# ModuloQuimica.net
KiCad netlist of a schematic drawn in Altium Designer
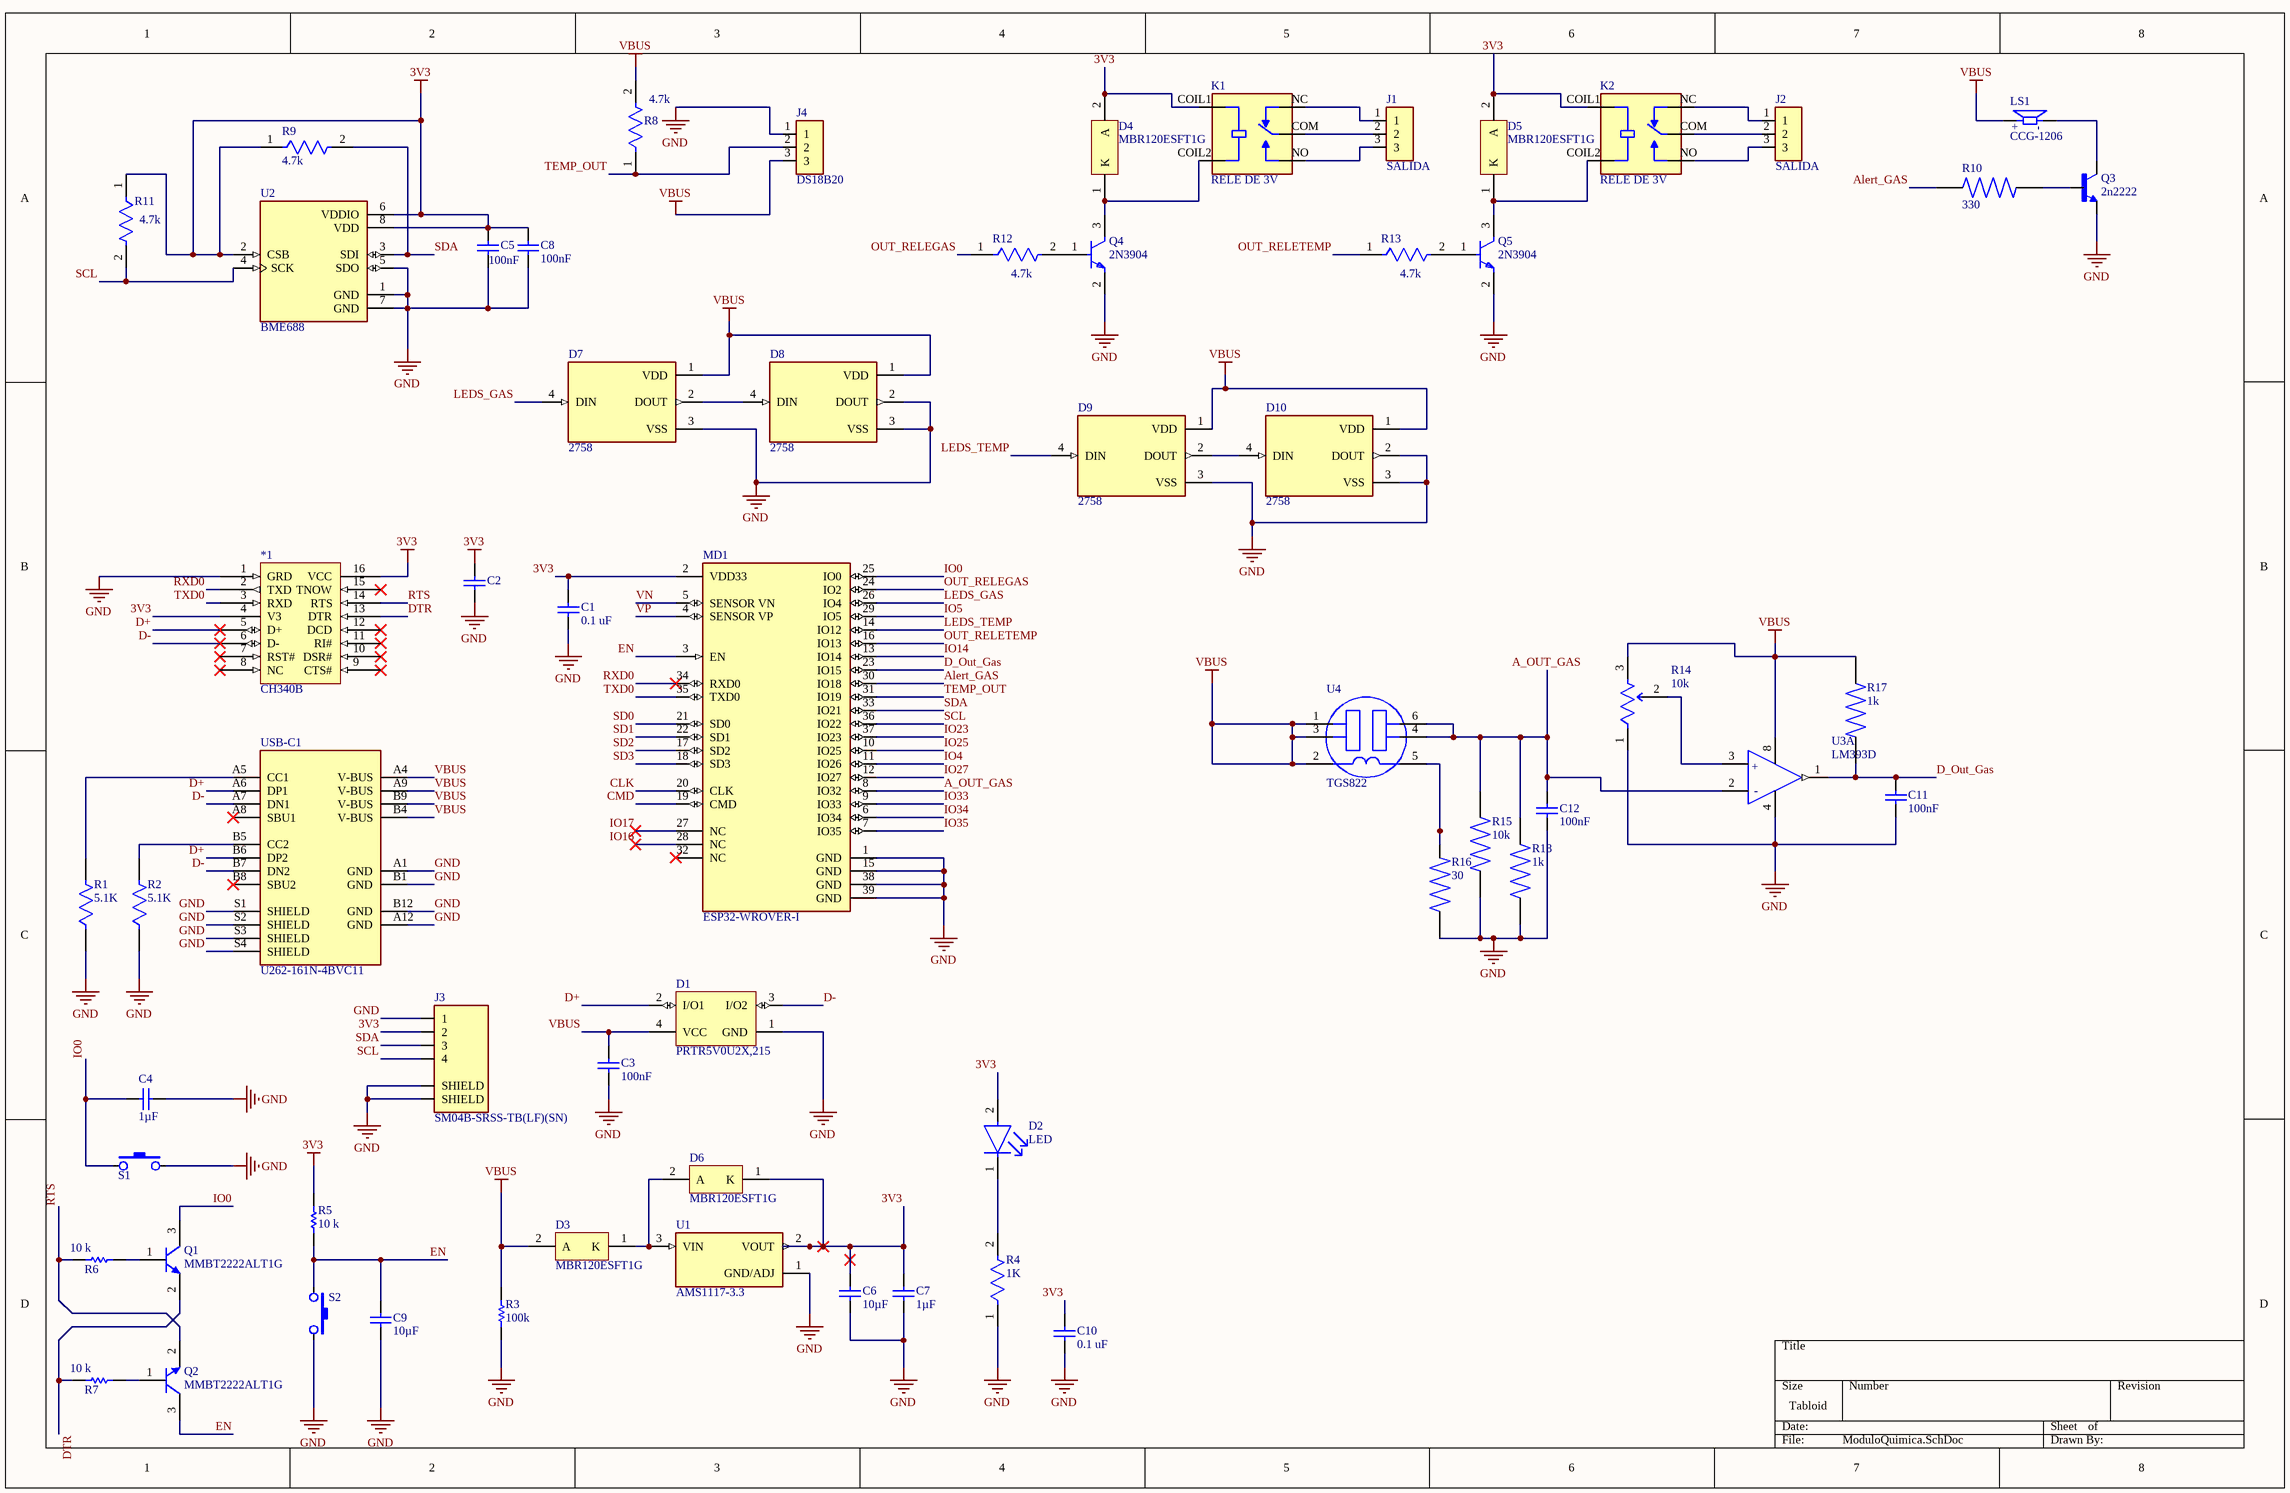
[diagram p0: ModuloQuimica.SchDoc]

(export (version "E")
  (design (tool "Eeschema 10.0.6"))
  (components
    (comp (ref "*1")
      (value "CH340B")
      (footprint "CH340B")
      (description "- USB 2.0 Transceiver 2Mbps SOP-16_150mil USB ICs ROHS")
      (libsource (lib "Isidro_Library") (part "CH340B"))
    )
    (comp (ref "C1")
      (value "0.1 uF")
      (footprint "CAPC2013X94X50ML20T25")
      (description "Chip Capacitor, Ceramic, 0.1 uF, 10%, 50 V, 0805, RoHS, Tape and Reel")
      (fields (field (name "MANUFACTURER") "AVX"))
      (libsource (lib "Altium Content Vault") (part "CAP-NP-2"))
    )
    (comp (ref "C2")
      (value "08055C104KAT2A")
      (footprint "CAPC2013X94X50ML20T25")
      (description "Chip Capacitor, Ceramic, 0.1 uF, 10%, 50 V, 0805, RoHS, Tape and Reel")
      (fields (field (name "MANUFACTURER") "AVX"))
      (libsource (lib "Altium Content Vault") (part "CAP-NP-2"))
    )
    (comp (ref "C3")
      (value "100nF")
      (footprint "CAPC2013X94X50ML20T25")
      (description "Chip Capacitor, Ceramic, 0.1 uF, 10%, 50 V, 0805, RoHS, Tape and Reel")
      (fields (field (name "MANUFACTURER") "AVX"))
      (libsource (lib "Altium Content Vault") (part "CAP-NP-2"))
    )
    (comp (ref "C4")
      (value "1µF")
      (footprint "CAPC2013X145X50ML20T25")
      (description "1µF ±10% 16V Ceramic Capacitor X7R 0805 (2012 Metric)")
      (fields (field (name "MANUFACTURER") "Kemet") (field (name "PART NUMBER") "C0805C105K4RAC7800"))
      (libsource (lib "Altium Content Vault") (part "CAP"))
    )
    (comp (ref "C5")
      (value "100nF")
      (footprint "CAPC2013X145X20LL20")
      (description "Chip Capacitor, 0.1 uF, +/- 10%, 50 V, -55 to 125 degC, 0805 (2012 Metric), RoHS, Tape and Reel")
      (fields (field (name "MANUFACTURER") "TDK") (field (name "VOLTAGE") "50V"))
      (libsource (lib "Altium Content Vault") (part "CAP-NP-2"))
    )
    (comp (ref "C6")
      (value "10µF")
      (footprint "CAPC2013X140X50ML20T25")
      (description "10µF ±10% 16V Ceramic Capacitor X5R 0805 (2012 Metric)")
      (fields (field (name "PART NUMBER") "CL21A106KOQNNNG"))
      (libsource (lib "Altium Content Vault") (part "CAP"))
    )
    (comp (ref "C7")
      (value "1µF")
      (footprint "CAPC2013X145X50ML20T25")
      (description "1µF ±10% 16V Ceramic Capacitor X7R 0805 (2012 Metric)")
      (fields (field (name "MANUFACTURER") "Kemet") (field (name "PART NUMBER") "C0805C105K4RAC7800"))
      (libsource (lib "Altium Content Vault") (part "CAP"))
    )
    (comp (ref "C8")
      (value "100nF")
      (footprint "CAPC2013X145X20LL20")
      (description "Chip Capacitor, 0.1 uF, +/- 10%, 50 V, -55 to 125 degC, 0805 (2012 Metric), RoHS, Tape and Reel")
      (fields (field (name "MANUFACTURER") "TDK") (field (name "VOLTAGE") "50V"))
      (libsource (lib "Altium Content Vault") (part "CAP-NP-2"))
    )
    (comp (ref "C9")
      (value "10µF")
      (footprint "CAPC2013X145X50ML20T25")
      (description "1µF ±10% 16V Ceramic Capacitor X7R 0805 (2012 Metric)")
      (fields (field (name "MANUFACTURER") "Kemet") (field (name "PART NUMBER") "C0805C105K4RAC7800"))
      (libsource (lib "Altium Content Vault") (part "CAP"))
    )
    (comp (ref "C10")
      (value "0.1 uF")
      (footprint "CAPC2013X94X50ML20T25")
      (description "Chip Capacitor, Ceramic, 0.1 uF, 10%, 50 V, 0805, RoHS, Tape and Reel")
      (fields (field (name "MANUFACTURER") "AVX"))
      (libsource (lib "Altium Content Vault") (part "CAP-NP-2"))
    )
    (comp (ref "C11")
      (value "100nF")
      (footprint "CAPC2013X145X20LL20")
      (description "Chip Capacitor, 0.1 uF, +/- 10%, 50 V, -55 to 125 degC, 0805 (2012 Metric), RoHS, Tape and Reel")
      (fields (field (name "MANUFACTURER") "TDK") (field (name "VOLTAGE") "50V"))
      (libsource (lib "Altium Content Vault") (part "CAP-NP-2"))
    )
    (comp (ref "C12")
      (value "100nF")
      (footprint "CAPC2013X145X20LL20")
      (description "Chip Capacitor, 0.1 uF, +/- 10%, 50 V, -55 to 125 degC, 0805 (2012 Metric), RoHS, Tape and Reel")
      (fields (field (name "MANUFACTURER") "TDK") (field (name "VOLTAGE") "50V"))
      (libsource (lib "Altium Content Vault") (part "CAP-NP-2"))
    )
    (comp (ref "D1")
      (value "PRTR5V0U2X,215")
      (footprint "NXP-SOT143B-4_V")
      (fields (field (name "MANUFACTURER") "NXP Semiconductors"))
      (libsource (lib "Altium Content Vault") (part "NXP-PRTR5V0U2X,215-4"))
    )
    (comp (ref "D2")
      (value "LED")
      (footprint "FP-HSMG-C150-MFG")
      (description "LED GREEN DIFFUSED 1206 SMD")
      (fields (field (name "MANUFACTURER PART NUMBER") "HSMG-C150") (field (name "MANUFACTURER") "Broadcom"))
      (libsource (lib "Altium Content Vault") (part "8706943c75ba83719d021d2fdc84c58"))
    )
    (comp (ref "D3")
      (value "MBR120ESFT1G")
      (footprint "ONSC-SOD-123FL-2-498_V")
      (description "Schottky Power Rectifier, 2-Pin SOD-123, Pb-Free, Tape and Reel")
      (fields (field (name "MANUFACTURER") "On Semiconductor"))
      (libsource (lib "Altium Content Vault") (part "ONSC-D-K1A2-2_A"))
    )
    (comp (ref "D4")
      (value "MBR120ESFT1G")
      (footprint "ONSC-SOD-123FL-2-498_V")
      (description "Schottky Power Rectifier, 2-Pin SOD-123, Pb-Free, Tape and Reel")
      (fields (field (name "MANUFACTURER") "On Semiconductor"))
      (libsource (lib "") (part "ONSC-D-K1A2-2_A_1"))
    )
    (comp (ref "D5")
      (value "MBR120ESFT1G")
      (footprint "ONSC-SOD-123FL-2-498_V")
      (description "Schottky Power Rectifier, 2-Pin SOD-123, Pb-Free, Tape and Reel")
      (fields (field (name "MANUFACTURER") "On Semiconductor"))
      (libsource (lib "") (part "ONSC-D-K1A2-2_A_1"))
    )
    (comp (ref "D6")
      (value "MBR120ESFT1G")
      (footprint "ONSC-SOD-123FL-2-498_V")
      (description "Schottky Power Rectifier, 2-Pin SOD-123, Pb-Free, Tape and Reel")
      (fields (field (name "MANUFACTURER") "On Semiconductor"))
      (libsource (lib "Altium Content Vault") (part "ONSC-D-K1A2-2_A"))
    )
    (comp (ref "D7")
      (value "2758")
      (footprint "SOL320P540X170-4N")
      (description "NeoPixel RGBW LEDs w/ Integrated DriverChip - Natural White - 4500K - White Ca")
      (fields (field (name "MF") "Adafruit Industries"))
      (libsource (lib "2758") (part "2758"))
    )
    (comp (ref "D8")
      (value "2758")
      (footprint "SOL320P540X170-4N")
      (description "NeoPixel RGBW LEDs w/ Integrated DriverChip - Natural White - 4500K - White Ca")
      (fields (field (name "MF") "Adafruit Industries"))
      (libsource (lib "2758") (part "2758"))
    )
    (comp (ref "D9")
      (value "2758")
      (footprint "SOL320P540X170-4N")
      (description "NeoPixel RGBW LEDs w/ Integrated DriverChip - Natural White - 4500K - White Ca")
      (fields (field (name "MF") "Adafruit Industries"))
      (libsource (lib "2758") (part "2758"))
    )
    (comp (ref "D10")
      (value "2758")
      (footprint "SOL320P540X170-4N")
      (description "NeoPixel RGBW LEDs w/ Integrated DriverChip - Natural White - 4500K - White Ca")
      (fields (field (name "MF") "Adafruit Industries"))
      (libsource (lib "2758") (part "2758"))
    )
    (comp (ref "J1")
      (value "SALIDA")
      (footprint "TE_282836-3")
      (description "TERM BLOCK 3POS SIDE ENTRY 5MM")
      (fields (field (name "MP") "282836-3"))
      (libsource (lib "282836-3") (part "282836-3"))
    )
    (comp (ref "J2")
      (value "SALIDA")
      (footprint "TE_282836-3")
      (description "TERM BLOCK 3POS SIDE ENTRY 5MM")
      (fields (field (name "MP") "282836-3"))
      (libsource (lib "282836-3") (part "282836-3"))
    )
    (comp (ref "J3")
      (value "SM04B-SRSS-TB(LF)(SN)")
      (footprint "JST_SM04B-SRSS-TB(LF)(SN)")
      (description "Connector Header Surface Mount, Right Angle 4 position 0.039 _1.00mm_")
      (fields (field (name "MF") "JST Sales") (field (name "MP") "SM04B-SRSS-TB_LF__SN_"))
      (libsource (lib "Isidro_Library") (part "SM04B-SRSS-TB(LF)(SN)"))
    )
    (comp (ref "J4")
      (value "DS18B20")
      (footprint "TE_282836-3")
      (description "TERM BLOCK 3POS SIDE ENTRY 5MM")
      (fields (field (name "MP") "282836-3"))
      (libsource (lib "282836-3") (part "282836-3"))
    )
    (comp (ref "K1")
      (value "RELE DE 3V")
      (footprint "RELAY_SRD-03VDC-SL-C")
      (description "Relays General Purpose Non Latching 3VDC SPDT 10A (250VAC) Max 5PIN")
      (fields (field (name "MF") "Songle Relay") (field (name "MP") "SRD-03VDC-SL-C"))
      (libsource (lib "SRD-03VDC-SL-C (1)") (part "SRD-03VDC-SL-C"))
    )
    (comp (ref "K2")
      (value "RELE DE 3V")
      (footprint "RELAY_SRD-03VDC-SL-C")
      (description "Relays General Purpose Non Latching 3VDC SPDT 10A (250VAC) Max 5PIN")
      (fields (field (name "MF") "Songle Relay") (field (name "MP") "SRD-03VDC-SL-C"))
      (libsource (lib "SRD-03VDC-SL-C (1)") (part "SRD-03VDC-SL-C"))
    )
    (comp (ref "LS1")
      (value "CCG-1206")
      (footprint "CUI_CCG-1206")
      (description "12 mm, 5 V, 85 dB, Through Hole, Sealed, Magnetic Audio Transducer Buzzer")
      (fields (field (name "MF") "Same Sky"))
      (libsource (lib "CCG-1206") (part "CCG-1206"))
    )
    (comp (ref "MD1")
      (value "ESP32-WROVER-I")
      (footprint "FP-ESP32-WROVER-I-MFG")
      (description "SMD MODULE, ESP32-D0WDQ6, 32MBIT")
      (fields
        (field (name "MANUFACTURER") "Espressif")
        (field (name "OCTOPART") "https://octopart.com/esp32-wrover-i-espressif+systems-89171349")
      )
      (libsource (lib "Altium Content Vault") (part "cbbb37af8bcfe61dfd46ac9418f0340"))
    )
    (comp (ref "Q1")
      (value "MMBT2222ALT1G")
      (footprint "ONSC-SOT-23-3-318-08_V")
      (description "General Purpose Transistor, NPN Silicon, 3-Pin SOT-23, Pb-Free, Tape and Reel")
      (fields (field (name "MANUFACTURER") "On Semiconductor"))
      (libsource (lib "Altium Content Vault") (part "ONSC-NPN-B1E2C3-3"))
    )
    (comp (ref "Q2")
      (value "MMBT2222ALT1G")
      (footprint "ONSC-SOT-23-3-318-08_V")
      (description "General Purpose Transistor, NPN Silicon, 3-Pin SOT-23, Pb-Free, Tape and Reel")
      (fields (field (name "MANUFACTURER") "On Semiconductor"))
      (libsource (lib "Altium Content Vault") (part "ONSC-NPN-B1E2C3-3"))
    )
    (comp (ref "Q3")
      (value "2n2222")
      (footprint "SOT95P240X120-3N")
      (description "BJT, SOT-23, 40V, 600mA, NPN, 0.25W, 150Â°C")
      (fields (field (name "MF") "Diotec Semiconductor") (field (name "MP") "MMBT2222A"))
      (libsource (lib "MMBT2222A") (part "MMBT2222A"))
    )
    (comp (ref "Q4")
      (value "2N3904")
      (footprint "FP-SS8050-G-MFG")
      (description "NPN TRANSISTOR 1.5A 40V SOT-23 R")
      (libsource (lib "Altium Content Vault") (part "2a1388f82443b098dcd57d24ac7632d"))
    )
    (comp (ref "Q5")
      (value "2N3904")
      (footprint "FP-SS8050-G-MFG")
      (description "NPN TRANSISTOR 1.5A 40V SOT-23 R")
      (libsource (lib "Altium Content Vault") (part "2a1388f82443b098dcd57d24ac7632d"))
    )
    (comp (ref "R1")
      (value "5.1K")
      (footprint "FP-CRCW0805-e3-MFG")
      (description "RES Thick Film, 5.1kΩ, 1%, 0.125W, 100ppm/°C, 0805")
      (fields (field (name "TOLERANCE") "1%"))
      (libsource (lib "Altium Content Vault") (part "1029c3af85768c4190bb7ad29bc67b5"))
    )
    (comp (ref "R2")
      (value "5.1K")
      (footprint "FP-CRCW0805-e3-MFG")
      (description "RES Thick Film, 5.1kΩ, 1%, 0.125W, 100ppm/°C, 0805")
      (fields (field (name "TOLERANCE") "1%"))
      (libsource (lib "Altium Content Vault") (part "1029c3af85768c4190bb7ad29bc67b5"))
    )
    (comp (ref "R3")
      (value "100k")
      (footprint "RESC2013X60X40ML20T25")
      (description "100 kOhms ±0.1% 0.125W, 1/8W Chip Resistor 0805 (2012 Metric) Automotive AEC-Q200 Thin Film")
      (fields (field (name "PART NUMBER") "ERA6AEB104V") (field (name "MANUFACTURER") "Panasonic"))
      (libsource (lib "Altium Content Vault") (part "RES"))
    )
    (comp (ref "R4")
      (value "1K")
      (footprint "FP-RP732A-MFG")
      (description "RESISTOR, 0805 80.6Ω, 0.1% 15ppm/°C")
      (fields
        (field (name "OCTOPART") "https://octopart.com/rp73d2a80r6btg-te+connectivity-42011633")
        (field (name "MANUFACTURER") "TE Connectivity")
      )
      (libsource (lib "") (part "1029c3af85768c4190bb7ad29bc67b5_1"))
    )
    (comp (ref "R5")
      (value "10 k")
      (footprint "RESC2013X60X30ML20T20")
      (fields (field (name "PART NUMBER") "RK73B2ATTD103J") (field (name "MANUFACTURER") "KOA Speer"))
      (libsource (lib "Altium Content Vault") (part "RES"))
    )
    (comp (ref "R6")
      (value "10 k")
      (footprint "RESC2013X60X30ML20T20")
      (fields (field (name "PART NUMBER") "RK73B2ATTD103J") (field (name "MANUFACTURER") "KOA Speer"))
      (libsource (lib "Altium Content Vault") (part "RES"))
    )
    (comp (ref "R7")
      (value "10 k")
      (footprint "RESC2013X60X30ML20T20")
      (fields (field (name "PART NUMBER") "RK73B2ATTD103J") (field (name "MANUFACTURER") "KOA Speer"))
      (libsource (lib "Altium Content Vault") (part "RES"))
    )
    (comp (ref "R8")
      (value "4.7k")
      (footprint "FP-CR1206-MFG")
      (description "Thick Film Chip Resistors 1206 4.7kΩ 0.25W 1% 100ppm/°C")
      (fields (field (name "TOLERANCE") "1%"))
      (libsource (lib "") (part "1029c3af85768c4190bb7ad29bc67b5_1"))
    )
    (comp (ref "R9")
      (value "4.7k")
      (footprint "FP-CR1206-MFG")
      (description "Thick Film Chip Resistors 1206 4.7kΩ 0.25W 1% 100ppm/°C")
      (fields (field (name "TOLERANCE") "1%"))
      (libsource (lib "") (part "1029c3af85768c4190bb7ad29bc67b5_1"))
    )
    (comp (ref "R10")
      (value "330")
      (footprint "RESC3015X65N")
      (description "330 Ohms Â±5% 0.25W, 1/4W Chip Resistor 1206 (3216 Metric) Thick Film")
      (fields (field (name "MF") "Vishay") (field (name "MP") "CRCW1206330RJNEAC"))
      (libsource (lib "CRCW1206330RJNEAC") (part "CRCW1206330RJNEAC"))
    )
    (comp (ref "R11")
      (value "4.7k")
      (footprint "FP-CR1206-MFG")
      (description "Thick Film Chip Resistors 1206 4.7kΩ 0.25W 1% 100ppm/°C")
      (fields (field (name "TOLERANCE") "1%"))
      (libsource (lib "") (part "1029c3af85768c4190bb7ad29bc67b5_1"))
    )
    (comp (ref "R12")
      (value "4.7k")
      (footprint "FP-CR1206-MFG")
      (description "Thick Film Chip Resistors 1206 4.7kΩ 0.25W 1% 100ppm/°C")
      (fields (field (name "TOLERANCE") "1%"))
      (libsource (lib "") (part "1029c3af85768c4190bb7ad29bc67b5_1"))
    )
    (comp (ref "R13")
      (value "4.7k")
      (footprint "FP-CR1206-MFG")
      (description "Thick Film Chip Resistors 1206 4.7kΩ 0.25W 1% 100ppm/°C")
      (fields (field (name "TOLERANCE") "1%"))
      (libsource (lib "") (part "1029c3af85768c4190bb7ad29bc67b5_1"))
    )
    (comp (ref "R14")
      (value "10k")
      (footprint "FP-3296Y-MFG")
      (description "TRIMMER 10K OHM 0.5W PC PIN TOP")
      (fields (field (name "TOLERANCE") "10%"))
      (libsource (lib "Altium Content Vault") (part "2dcfd2547301a7d3209a5e99acfd772"))
    )
    (comp (ref "R15")
      (value "10k")
      (footprint "RESC3116X65N")
      (description "10 Ohms Â±1% 0.25W, 1/4W Chip Resistor 1206 (3216 Metric) Moisture Resistant Thick Film")
      (fields (field (name "MP") "RC1206FR-0710RL") (field (name "MF") "Yageo"))
      (libsource (lib "RC1206FR-0710RL") (part "RC1206FR-0710RL"))
    )
    (comp (ref "R16")
      (value "30")
      (footprint "RESC2012X60N")
      (description "Res Thick Film 0805 10 Ohm 1% 1/8W ï¿½200ppm/ï¿½C Molded SMD Paper T/R")
      (fields (field (name "MF") "{'manufacturer': u'YAGEO'}") (field (name "MP") "RC0805FR-0710RL"))
      (libsource (lib "RC0805FR-0710RL") (part "RC0805FR-0710RL"))
    )
    (comp (ref "R17")
      (value "1k")
      (footprint "RESC3116X65N")
      (description "10 Ohms Â±1% 0.25W, 1/4W Chip Resistor 1206 (3216 Metric) Moisture Resistant Thick Film")
      (fields (field (name "MP") "RC1206FR-0710RL") (field (name "MF") "Yageo"))
      (libsource (lib "RC1206FR-0710RL") (part "RC1206FR-0710RL"))
    )
    (comp (ref "R18")
      (value "1k")
      (footprint "RESC3116X65N")
      (description "10 Ohms Â±1% 0.25W, 1/4W Chip Resistor 1206 (3216 Metric) Moisture Resistant Thick Film")
      (fields (field (name "MP") "RC1206FR-0710RL") (field (name "MF") "Yageo"))
      (libsource (lib "RC1206FR-0710RL") (part "RC1206FR-0710RL"))
    )
    (comp (ref "S1")
      (value "IO0")
      (footprint "SMT_SW_PTS_820")
      (libsource (lib "SnapEDAsch") (part "PTS820J25MSMTRLFS"))
    )
    (comp (ref "S2")
      (value "PTS820J25MSMTRLFS")
      (footprint "SMT_SW_PTS_820")
      (libsource (lib "SnapEDAsch") (part "PTS820J25MSMTRLFS"))
    )
    (comp (ref "U1")
      (value "AMS1117-3.3")
      (footprint "SOT229P700X180-4N")
      (description "Sot223/Pkg 1-Amp 3.3-Volt Low Drop Out Voltage Regulatator")
      (fields (field (name "MF") "Advanced Monolithic Systems"))
      (libsource (lib "AMS1117-3.3") (part "AMS1117-3.3"))
    )
    (comp (ref "U2")
      (value "BME688")
      (footprint "IC_BME688")
      (description "Gas sensor measuring relative humidity, barometric pressure, ambient temperature and gas (VOC)")
      (libsource (lib "BME688") (part "BME688"))
    )
    (comp (ref "U3")
      (value "LM393D")
      (footprint "FP-SO8-MFG")
      (description "IC VOLT COMPARATOR DUAL LP 8SOIC")
      (fields
        (field (name "OCTOPART") "https://octopart.com/lm393d-stmicroelectronics-25832")
        (field (name "MANUFACTURER") "STMicroelectronics")
      )
      (libsource (lib "Altium Content Vault") (part "de625b5ab9e10f2679b51f9a3a11a5f"))
    )
    (comp (ref "U4")
      (value "TGS822")
      (footprint "FP-TGS822-MFG")
      (description "TGS822 MOS-Type organic solvent vapors sensor; range: 50-5000ppm C2H5OH; supply: 5V; power: 660mW")
      (libsource (lib "Altium Content Vault") (part "177b91c4a673ff2773236b1cb9aa546"))
    )
    (comp (ref "USB-C1")
      (value "U262-161N-4BVC11")
      (footprint "U262-161N-4BVC11")
      (description "USB - Type C Female 16 SMT USB Connectors RoHS")
      (libsource (lib "AQIMon") (part "U262-161N-4BVC11"))
    )
  )
  (nets
    (net (code "1") (name "/A_OUT_GAS") (class "Default")
      (node (ref "C12") (pin "2") (pinfunction "2_2") (pintype "passive"))
      (node (ref "MD1") (pin "8") (pinfunction "IO32_8") (pintype "bidirectional"))
      (node (ref "R15") (pin "2") (pinfunction "2_2") (pintype "passive"))
      (node (ref "R18") (pin "2") (pinfunction "2_2") (pintype "passive"))
      (node (ref "U3") (pin "2") (pinfunction "In1-_2") (pintype "tri_state"))
      (node (ref "U4") (pin "4") (pinfunction "VRL_4") (pintype "passive"))
      (node (ref "U4") (pin "6") (pinfunction "VRL_6") (pintype "passive"))
    )
    (net (code "2") (name "/Alert_GAS") (class "Default")
      (node (ref "MD1") (pin "30") (pinfunction "IO18_30") (pintype "bidirectional"))
      (node (ref "R10") (pin "1") (pinfunction "1_1") (pintype "passive"))
    )
    (net (code "3") (name "/CLK") (class "Default")
      (node (ref "MD1") (pin "20") (pinfunction "CLK_20") (pintype "bidirectional"))
    )
    (net (code "4") (name "/CMD") (class "Default")
      (node (ref "MD1") (pin "19") (pinfunction "CMD_19") (pintype "bidirectional"))
    )
    (net (code "5") (name "/D+") (class "Default")
      (node (ref "*1") (pin "5") (pinfunction "D+_5") (pintype "bidirectional"))
      (node (ref "D1") (pin "2") (pinfunction "I/O1_2") (pintype "bidirectional"))
      (node (ref "USB-C1") (pin "A6") (pinfunction "DP1_A6") (pintype "power_in"))
      (node (ref "USB-C1") (pin "B6") (pinfunction "DP2_B6") (pintype "power_in"))
    )
    (net (code "6") (name "/D-") (class "Default")
      (node (ref "*1") (pin "6") (pinfunction "D-_6") (pintype "bidirectional"))
      (node (ref "D1") (pin "3") (pinfunction "I/O2_3") (pintype "bidirectional"))
      (node (ref "USB-C1") (pin "A7") (pinfunction "DN1_A7") (pintype "power_in"))
      (node (ref "USB-C1") (pin "B7") (pinfunction "DN2_B7") (pintype "power_in"))
    )
    (net (code "7") (name "/DTR") (class "Default")
      (node (ref "*1") (pin "13") (pinfunction "DTR_13") (pintype "input"))
      (node (ref "Q1") (pin "2") (pinfunction "E_2") (pintype "passive"))
      (node (ref "R7") (pin "2") (pinfunction "2_2") (pintype "passive"))
    )
    (net (code "8") (name "/D_Out_Gas") (class "Default")
      (node (ref "C11") (pin "2") (pinfunction "2_2") (pintype "passive"))
      (node (ref "MD1") (pin "23") (pinfunction "IO15_23") (pintype "bidirectional"))
      (node (ref "R17") (pin "1") (pinfunction "1_1") (pintype "passive"))
      (node (ref "U3") (pin "1") (pinfunction "Out1_1") (pintype "output"))
    )
    (net (code "9") (name "/EN") (class "Default")
      (node (ref "C9") (pin "2") (pinfunction "2_2") (pintype "passive"))
      (node (ref "MD1") (pin "3") (pinfunction "EN_3") (pintype "input"))
      (node (ref "Q2") (pin "3") (pinfunction "C_3") (pintype "passive"))
      (node (ref "R5") (pin "1") (pinfunction "1_1") (pintype "passive"))
      (node (ref "S2") (pin "1") (pinfunction "1_1") (pintype "passive"))
    )
    (net (code "10") (name "/IO0") (class "Default")
      (node (ref "C4") (pin "2") (pinfunction "2_2") (pintype "passive"))
      (node (ref "MD1") (pin "25") (pinfunction "IO0_25") (pintype "bidirectional"))
      (node (ref "Q1") (pin "3") (pinfunction "C_3") (pintype "passive"))
      (node (ref "S1") (pin "1") (pinfunction "1_1") (pintype "passive"))
    )
    (net (code "11") (name "/IO4") (class "Default")
      (node (ref "MD1") (pin "11") (pinfunction "IO26_11") (pintype "bidirectional"))
    )
    (net (code "12") (name "/IO5") (class "Default")
      (node (ref "MD1") (pin "29") (pinfunction "IO5_29") (pintype "bidirectional"))
    )
    (net (code "13") (name "/IO14") (class "Default")
      (node (ref "MD1") (pin "13") (pinfunction "IO14_13") (pintype "bidirectional"))
    )
    (net (code "14") (name "/IO16") (class "Default")
      (node (ref "MD1") (pin "28") (pinfunction "NC_28") (pintype "passive+no_connect"))
    )
    (net (code "15") (name "/IO17") (class "Default")
      (node (ref "MD1") (pin "27") (pinfunction "NC_27") (pintype "passive+no_connect"))
    )
    (net (code "16") (name "/IO23") (class "Default")
      (node (ref "MD1") (pin "37") (pinfunction "IO23_37") (pintype "bidirectional"))
    )
    (net (code "17") (name "/IO25") (class "Default")
      (node (ref "MD1") (pin "10") (pinfunction "IO25_10") (pintype "bidirectional"))
    )
    (net (code "18") (name "/IO27") (class "Default")
      (node (ref "MD1") (pin "12") (pinfunction "IO27_12") (pintype "bidirectional"))
    )
    (net (code "19") (name "/IO33") (class "Default")
      (node (ref "MD1") (pin "9") (pinfunction "IO33_9") (pintype "bidirectional"))
    )
    (net (code "20") (name "/IO34") (class "Default")
      (node (ref "MD1") (pin "6") (pinfunction "IO34_6") (pintype "bidirectional"))
    )
    (net (code "21") (name "/IO35") (class "Default")
      (node (ref "MD1") (pin "7") (pinfunction "IO35_7") (pintype "bidirectional"))
    )
    (net (code "22") (name "/LEDS_GAS") (class "Default")
      (node (ref "D7") (pin "4") (pinfunction "DIN_4") (pintype "input"))
      (node (ref "MD1") (pin "26") (pinfunction "IO4_26") (pintype "bidirectional"))
    )
    (net (code "23") (name "/LEDS_TEMP") (class "Default")
      (node (ref "D9") (pin "4") (pinfunction "DIN_4") (pintype "input"))
      (node (ref "MD1") (pin "14") (pinfunction "IO12_14") (pintype "bidirectional"))
    )
    (net (code "24") (name "/OUT_RELEGAS") (class "Default")
      (node (ref "MD1") (pin "24") (pinfunction "IO2_24") (pintype "bidirectional"))
      (node (ref "R12") (pin "1") (pinfunction "1_1") (pintype "passive"))
    )
    (net (code "25") (name "/OUT_RELETEMP") (class "Default")
      (node (ref "MD1") (pin "16") (pinfunction "IO13_16") (pintype "bidirectional"))
      (node (ref "R13") (pin "1") (pinfunction "1_1") (pintype "passive"))
    )
    (net (code "26") (name "/RTS") (class "Default")
      (node (ref "*1") (pin "14") (pinfunction "RTS_14") (pintype "input"))
      (node (ref "Q2") (pin "2") (pinfunction "E_2") (pintype "passive"))
      (node (ref "R6") (pin "2") (pinfunction "2_2") (pintype "passive"))
    )
    (net (code "27") (name "/RXD0") (class "Default")
      (node (ref "*1") (pin "2") (pinfunction "TXD_2") (pintype "output"))
      (node (ref "MD1") (pin "34") (pinfunction "RXD0_34") (pintype "bidirectional"))
    )
    (net (code "28") (name "/SCL") (class "Default")
      (node (ref "J3") (pin "4") (pinfunction "4_4") (pintype "passive"))
      (node (ref "MD1") (pin "36") (pinfunction "IO22_36") (pintype "bidirectional"))
      (node (ref "R11") (pin "2") (pinfunction "2_2") (pintype "passive"))
      (node (ref "U2") (pin "4") (pinfunction "SCK_4") (pintype "input"))
    )
    (net (code "29") (name "/SD0") (class "Default")
      (node (ref "MD1") (pin "21") (pinfunction "SD0_21") (pintype "bidirectional"))
    )
    (net (code "30") (name "/SD1") (class "Default")
      (node (ref "MD1") (pin "22") (pinfunction "SD1_22") (pintype "bidirectional"))
    )
    (net (code "31") (name "/SD2") (class "Default")
      (node (ref "MD1") (pin "17") (pinfunction "SD2_17") (pintype "bidirectional"))
    )
    (net (code "32") (name "/SD3") (class "Default")
      (node (ref "MD1") (pin "18") (pinfunction "SD3_18") (pintype "bidirectional"))
    )
    (net (code "33") (name "/SDA") (class "Default")
      (node (ref "J3") (pin "3") (pinfunction "3_3") (pintype "passive"))
      (node (ref "MD1") (pin "33") (pinfunction "IO21_33") (pintype "bidirectional"))
      (node (ref "R9") (pin "2") (pinfunction "2_2") (pintype "passive"))
      (node (ref "U2") (pin "3") (pinfunction "SDI_3") (pintype "bidirectional"))
    )
    (net (code "34") (name "/TEMP_OUT") (class "Default")
      (node (ref "J4") (pin "2") (pinfunction "2_2") (pintype "passive"))
      (node (ref "MD1") (pin "31") (pinfunction "IO19_31") (pintype "bidirectional"))
      (node (ref "R8") (pin "1") (pinfunction "1_1") (pintype "passive"))
    )
    (net (code "35") (name "/TXD0") (class "Default")
      (node (ref "*1") (pin "3") (pinfunction "RXD_3") (pintype "input"))
      (node (ref "MD1") (pin "35") (pinfunction "TXD0_35") (pintype "bidirectional"))
    )
    (net (code "36") (name "/VN") (class "Default")
      (node (ref "MD1") (pin "5") (pinfunction "SENSOR_VN_5") (pintype "bidirectional"))
    )
    (net (code "37") (name "/VP") (class "Default")
      (node (ref "MD1") (pin "4") (pinfunction "SENSOR_VP_4") (pintype "bidirectional"))
    )
    (net (code "38") (name "3V3") (class "Default")
      (node (ref "*1") (pin "16") (pinfunction "VCC_16") (pintype "power_in"))
      (node (ref "*1") (pin "4") (pinfunction "V3_4") (pintype "power_in"))
      (node (ref "C1") (pin "2") (pinfunction "2_2") (pintype "passive"))
      (node (ref "C10") (pin "2") (pinfunction "2_2") (pintype "passive"))
      (node (ref "C2") (pin "2") (pinfunction "2_2") (pintype "passive"))
      (node (ref "C5") (pin "2") (pinfunction "2_2") (pintype "passive"))
      (node (ref "C6") (pin "2") (pinfunction "2_2") (pintype "passive"))
      (node (ref "C7") (pin "2") (pinfunction "2_2") (pintype "passive"))
      (node (ref "C8") (pin "2") (pinfunction "2_2") (pintype "passive"))
      (node (ref "D2") (pin "2") (pinfunction "A_2") (pintype "passive"))
      (node (ref "D4") (pin "2") (pinfunction "A_2") (pintype "passive"))
      (node (ref "D5") (pin "2") (pinfunction "A_2") (pintype "passive"))
      (node (ref "D6") (pin "1") (pinfunction "K_1") (pintype "passive"))
      (node (ref "J3") (pin "2") (pinfunction "2_2") (pintype "passive"))
      (node (ref "K1") (pin "COIL1") (pinfunction "COIL1_COIL1") (pintype "passive"))
      (node (ref "K2") (pin "COIL1") (pinfunction "COIL1_COIL1") (pintype "passive"))
      (node (ref "MD1") (pin "2") (pinfunction "VDD33_2") (pintype "power_in"))
      (node (ref "R11") (pin "1") (pinfunction "1_1") (pintype "passive"))
      (node (ref "R5") (pin "2") (pinfunction "2_2") (pintype "passive"))
      (node (ref "R9") (pin "1") (pinfunction "1_1") (pintype "passive"))
      (node (ref "U1") (pin "2") (pinfunction "VOUT_2") (pintype "output"))
      (node (ref "U2") (pin "2") (pinfunction "CSB_2") (pintype "input"))
      (node (ref "U2") (pin "6") (pinfunction "VDDIO_6") (pintype "power_in"))
      (node (ref "U2") (pin "8") (pinfunction "VDD_8") (pintype "power_in"))
    )
    (net (code "39") (name "GND") (class "Default")
      (node (ref "*1") (pin "1") (pinfunction "GRD_1") (pintype "input"))
      (node (ref "C1") (pin "1") (pinfunction "1_1") (pintype "passive"))
      (node (ref "C10") (pin "1") (pinfunction "1_1") (pintype "passive"))
      (node (ref "C11") (pin "1") (pinfunction "1_1") (pintype "passive"))
      (node (ref "C12") (pin "1") (pinfunction "1_1") (pintype "passive"))
      (node (ref "C2") (pin "1") (pinfunction "1_1") (pintype "passive"))
      (node (ref "C3") (pin "1") (pinfunction "1_1") (pintype "passive"))
      (node (ref "C4") (pin "1") (pinfunction "1_1") (pintype "passive"))
      (node (ref "C5") (pin "1") (pinfunction "1_1") (pintype "passive"))
      (node (ref "C6") (pin "1") (pinfunction "1_1") (pintype "passive"))
      (node (ref "C7") (pin "1") (pinfunction "1_1") (pintype "passive"))
      (node (ref "C8") (pin "1") (pinfunction "1_1") (pintype "passive"))
      (node (ref "C9") (pin "1") (pinfunction "1_1") (pintype "passive"))
      (node (ref "D1") (pin "1") (pinfunction "GND_1") (pintype "power_in"))
      (node (ref "D10") (pin "2") (pinfunction "DOUT_2") (pintype "output"))
      (node (ref "D10") (pin "3") (pinfunction "VSS_3") (pintype "power_in"))
      (node (ref "D7") (pin "3") (pinfunction "VSS_3") (pintype "power_in"))
      (node (ref "D8") (pin "2") (pinfunction "DOUT_2") (pintype "output"))
      (node (ref "D8") (pin "3") (pinfunction "VSS_3") (pintype "power_in"))
      (node (ref "D9") (pin "3") (pinfunction "VSS_3") (pintype "power_in"))
      (node (ref "J3") (pin "1") (pinfunction "1_1") (pintype "passive"))
      (node (ref "J3") (pin "S1") (pinfunction "SHIELD_S1") (pintype "passive"))
      (node (ref "J3") (pin "S2") (pinfunction "SHIELD_S2") (pintype "passive"))
      (node (ref "J4") (pin "1") (pinfunction "1_1") (pintype "passive"))
      (node (ref "MD1") (pin "1") (pinfunction "GND_1") (pintype "power_in"))
      (node (ref "MD1") (pin "15") (pinfunction "GND_15") (pintype "power_in"))
      (node (ref "MD1") (pin "38") (pinfunction "GND_38") (pintype "power_in"))
      (node (ref "MD1") (pin "39") (pinfunction "GND_39") (pintype "power_in"))
      (node (ref "Q3") (pin "2") (pinfunction "E_2") (pintype "passive"))
      (node (ref "Q4") (pin "2") (pinfunction "E_2") (pintype "passive"))
      (node (ref "Q5") (pin "2") (pinfunction "E_2") (pintype "passive"))
      (node (ref "R1") (pin "1") (pinfunction "1_1") (pintype "passive"))
      (node (ref "R14") (pin "1") (pinfunction "CCW_1") (pintype "passive"))
      (node (ref "R15") (pin "1") (pinfunction "1_1") (pintype "passive"))
      (node (ref "R16") (pin "2") (pinfunction "2_2") (pintype "passive"))
      (node (ref "R18") (pin "1") (pinfunction "1_1") (pintype "passive"))
      (node (ref "R2") (pin "1") (pinfunction "1_1") (pintype "passive"))
      (node (ref "R3") (pin "1") (pinfunction "1_1") (pintype "passive"))
      (node (ref "R4") (pin "1") (pinfunction "1_1") (pintype "passive"))
      (node (ref "S1") (pin "2") (pinfunction "2_2") (pintype "passive"))
      (node (ref "S2") (pin "2") (pinfunction "2_2") (pintype "passive"))
      (node (ref "U1") (pin "1") (pinfunction "GND/ADJ_1") (pintype "power_in"))
      (node (ref "U2") (pin "1") (pinfunction "GND_1") (pintype "power_in"))
      (node (ref "U2") (pin "5") (pinfunction "SDO_5") (pintype "bidirectional"))
      (node (ref "U2") (pin "7") (pinfunction "GND_7") (pintype "power_in"))
      (node (ref "U3") (pin "4") (pinfunction "Vcc-_4") (pintype "power_in"))
      (node (ref "USB-C1") (pin "A1") (pinfunction "GND_A1") (pintype "power_in"))
      (node (ref "USB-C1") (pin "A12") (pinfunction "GND_A12") (pintype "power_in"))
      (node (ref "USB-C1") (pin "B1") (pinfunction "GND_B1") (pintype "power_in"))
      (node (ref "USB-C1") (pin "B12") (pinfunction "GND_B12") (pintype "power_in"))
      (node (ref "USB-C1") (pin "S1") (pinfunction "SHIELD_S1") (pintype "passive"))
      (node (ref "USB-C1") (pin "S2") (pinfunction "SHIELD_S2") (pintype "passive"))
      (node (ref "USB-C1") (pin "S3") (pinfunction "SHIELD_S3") (pintype "passive"))
      (node (ref "USB-C1") (pin "S4") (pinfunction "SHIELD_S4") (pintype "passive"))
    )
    (net (code "40") (name "Net-(D2-C)") (class "Default")
      (node (ref "D2") (pin "1") (pinfunction "C_1") (pintype "passive"))
      (node (ref "R4") (pin "2") (pinfunction "2_2") (pintype "passive"))
    )
    (net (code "41") (name "Net-(D3-K)") (class "Default")
      (node (ref "D3") (pin "1") (pinfunction "K_1") (pintype "passive"))
      (node (ref "D6") (pin "2") (pinfunction "A_2") (pintype "passive"))
      (node (ref "U1") (pin "3") (pinfunction "VIN_3") (pintype "input"))
    )
    (net (code "42") (name "Net-(D4-K)") (class "Default")
      (node (ref "D4") (pin "1") (pinfunction "K_1") (pintype "passive"))
      (node (ref "K1") (pin "COIL2") (pinfunction "COIL2_COIL2") (pintype "passive"))
      (node (ref "Q4") (pin "3") (pinfunction "C_3") (pintype "passive"))
    )
    (net (code "43") (name "Net-(D5-K)") (class "Default")
      (node (ref "D5") (pin "1") (pinfunction "K_1") (pintype "passive"))
      (node (ref "K2") (pin "COIL2") (pinfunction "COIL2_COIL2") (pintype "passive"))
      (node (ref "Q5") (pin "3") (pinfunction "C_3") (pintype "passive"))
    )
    (net (code "44") (name "Net-(D7-DOUT)") (class "Default")
      (node (ref "D7") (pin "2") (pinfunction "DOUT_2") (pintype "output"))
      (node (ref "D8") (pin "4") (pinfunction "DIN_4") (pintype "input"))
    )
    (net (code "45") (name "Net-(D10-DIN)") (class "Default")
      (node (ref "D10") (pin "4") (pinfunction "DIN_4") (pintype "input"))
      (node (ref "D9") (pin "2") (pinfunction "DOUT_2") (pintype "output"))
    )
    (net (code "46") (name "Net-(J1-Pad1)") (class "Default")
      (node (ref "J1") (pin "1") (pinfunction "1_1") (pintype "passive"))
      (node (ref "K1") (pin "NC") (pinfunction "NC_NC") (pintype "passive"))
    )
    (net (code "47") (name "Net-(J1-Pad2)") (class "Default")
      (node (ref "J1") (pin "2") (pinfunction "2_2") (pintype "passive"))
      (node (ref "K1") (pin "COM") (pinfunction "COM_COM") (pintype "passive"))
    )
    (net (code "48") (name "Net-(J1-Pad3)") (class "Default")
      (node (ref "J1") (pin "3") (pinfunction "3_3") (pintype "passive"))
      (node (ref "K1") (pin "NO") (pinfunction "NO_NO") (pintype "passive"))
    )
    (net (code "49") (name "Net-(J2-Pad1)") (class "Default")
      (node (ref "J2") (pin "1") (pinfunction "1_1") (pintype "passive"))
      (node (ref "K2") (pin "NC") (pinfunction "NC_NC") (pintype "passive"))
    )
    (net (code "50") (name "Net-(J2-Pad2)") (class "Default")
      (node (ref "J2") (pin "2") (pinfunction "2_2") (pintype "passive"))
      (node (ref "K2") (pin "COM") (pinfunction "COM_COM") (pintype "passive"))
    )
    (net (code "51") (name "Net-(J2-Pad3)") (class "Default")
      (node (ref "J2") (pin "3") (pinfunction "3_3") (pintype "passive"))
      (node (ref "K2") (pin "NO") (pinfunction "NO_NO") (pintype "passive"))
    )
    (net (code "52") (name "Net-(Q1-B)") (class "Default")
      (node (ref "Q1") (pin "1") (pinfunction "B_1") (pintype "passive"))
      (node (ref "R6") (pin "1") (pinfunction "1_1") (pintype "passive"))
    )
    (net (code "53") (name "Net-(Q2-B)") (class "Default")
      (node (ref "Q2") (pin "1") (pinfunction "B_1") (pintype "passive"))
      (node (ref "R7") (pin "1") (pinfunction "1_1") (pintype "passive"))
    )
    (net (code "54") (name "Net-(Q3-B)") (class "Default")
      (node (ref "Q3") (pin "1") (pinfunction "B_1") (pintype "passive"))
      (node (ref "R10") (pin "2") (pinfunction "2_2") (pintype "passive"))
    )
    (net (code "55") (name "Net-(Q3-C)") (class "Default")
      (node (ref "LS1") (pin "M") (pinfunction "M_M") (pintype "passive"))
      (node (ref "Q3") (pin "3") (pinfunction "C_3") (pintype "passive"))
    )
    (net (code "56") (name "Net-(Q4-B)") (class "Default")
      (node (ref "Q4") (pin "1") (pinfunction "B_1") (pintype "passive"))
      (node (ref "R12") (pin "2") (pinfunction "2_2") (pintype "passive"))
    )
    (net (code "57") (name "Net-(Q5-B)") (class "Default")
      (node (ref "Q5") (pin "1") (pinfunction "B_1") (pintype "passive"))
      (node (ref "R13") (pin "2") (pinfunction "2_2") (pintype "passive"))
    )
    (net (code "58") (name "Net-(R14-WIPER)") (class "Default")
      (node (ref "R14") (pin "2") (pinfunction "WIPER_2") (pintype "passive"))
      (node (ref "U3") (pin "3") (pinfunction "In1+_3") (pintype "tri_state"))
    )
    (net (code "59") (name "Net-(U4-GND)") (class "Default")
      (node (ref "R16") (pin "1") (pinfunction "1_1") (pintype "passive"))
      (node (ref "U4") (pin "5") (pinfunction "GND_5") (pintype "power_in"))
    )
    (net (code "60") (name "Net-(USB-C1-CC1)") (class "Default")
      (node (ref "R1") (pin "2") (pinfunction "2_2") (pintype "passive"))
      (node (ref "USB-C1") (pin "A5") (pinfunction "CC1_A5") (pintype "power_in"))
    )
    (net (code "61") (name "Net-(USB-C1-CC2)") (class "Default")
      (node (ref "R2") (pin "2") (pinfunction "2_2") (pintype "passive"))
      (node (ref "USB-C1") (pin "B5") (pinfunction "CC2_B5") (pintype "power_in"))
    )
    (net (code "62") (name "VBUS") (class "Default")
      (node (ref "C3") (pin "2") (pinfunction "2_2") (pintype "passive"))
      (node (ref "D1") (pin "4") (pinfunction "VCC_4") (pintype "power_in"))
      (node (ref "D10") (pin "1") (pinfunction "VDD_1") (pintype "power_in"))
      (node (ref "D3") (pin "2") (pinfunction "A_2") (pintype "passive"))
      (node (ref "D7") (pin "1") (pinfunction "VDD_1") (pintype "power_in"))
      (node (ref "D8") (pin "1") (pinfunction "VDD_1") (pintype "power_in"))
      (node (ref "D9") (pin "1") (pinfunction "VDD_1") (pintype "power_in"))
      (node (ref "J4") (pin "3") (pinfunction "3_3") (pintype "passive"))
      (node (ref "LS1") (pin "P") (pinfunction "P_P") (pintype "passive"))
      (node (ref "R14") (pin "3") (pinfunction "CW_3") (pintype "passive"))
      (node (ref "R17") (pin "2") (pinfunction "2_2") (pintype "passive"))
      (node (ref "R3") (pin "2") (pinfunction "2_2") (pintype "passive"))
      (node (ref "R8") (pin "2") (pinfunction "2_2") (pintype "passive"))
      (node (ref "U3") (pin "8") (pinfunction "Vcc+_8") (pintype "power_in"))
      (node (ref "U4") (pin "1") (pinfunction "VC_1") (pintype "power_in"))
      (node (ref "U4") (pin "2") (pinfunction "VH_2") (pintype "power_in"))
      (node (ref "U4") (pin "3") (pinfunction "VC_3") (pintype "power_in"))
      (node (ref "USB-C1") (pin "A4") (pinfunction "V-BUS_A4") (pintype "power_in"))
      (node (ref "USB-C1") (pin "A9") (pinfunction "V-BUS_A9") (pintype "power_in"))
      (node (ref "USB-C1") (pin "B4") (pinfunction "V-BUS_B4") (pintype "power_in"))
      (node (ref "USB-C1") (pin "B9") (pinfunction "V-BUS_B9") (pintype "power_in"))
    )
    (net (code "63") (name "unconnected-(*1-CTS#-Pad9)") (class "Default")
      (node (ref "*1") (pin "9") (pinfunction "CTS#_9") (pintype "input+no_connect"))
    )
    (net (code "64") (name "unconnected-(*1-DCD-Pad12)") (class "Default")
      (node (ref "*1") (pin "12") (pinfunction "DCD_12") (pintype "input+no_connect"))
    )
    (net (code "65") (name "unconnected-(*1-DSR#-Pad10)") (class "Default")
      (node (ref "*1") (pin "10") (pinfunction "DSR#_10") (pintype "input+no_connect"))
    )
    (net (code "66") (name "unconnected-(*1-NC-Pad8)") (class "Default")
      (node (ref "*1") (pin "8") (pinfunction "NC_8") (pintype "input+no_connect"))
    )
    (net (code "67") (name "unconnected-(*1-RI#-Pad11)") (class "Default")
      (node (ref "*1") (pin "11") (pinfunction "RI#_11") (pintype "input+no_connect"))
    )
    (net (code "68") (name "unconnected-(*1-RST#-Pad7)") (class "Default")
      (node (ref "*1") (pin "7") (pinfunction "RST#_7") (pintype "input+no_connect"))
    )
    (net (code "69") (name "unconnected-(*1-TNOW-Pad15)") (class "Default")
      (node (ref "*1") (pin "15") (pinfunction "TNOW_15") (pintype "input+no_connect"))
    )
    (net (code "70") (name "unconnected-(MD1-NC-Pad32)") (class "Default")
      (node (ref "MD1") (pin "32") (pinfunction "NC_32") (pintype "passive+no_connect"))
    )
    (net (code "71") (name "unconnected-(USB-C1-SBU1-PadA8)") (class "Default")
      (node (ref "USB-C1") (pin "A8") (pinfunction "SBU1_A8") (pintype "power_in+no_connect"))
    )
    (net (code "72") (name "unconnected-(USB-C1-SBU2-PadB8)") (class "Default")
      (node (ref "USB-C1") (pin "B8") (pinfunction "SBU2_B8") (pintype "power_in+no_connect"))
    )
  )
)
